# ROME.net
KiCad netlist of a schematic drawn in EAGLE
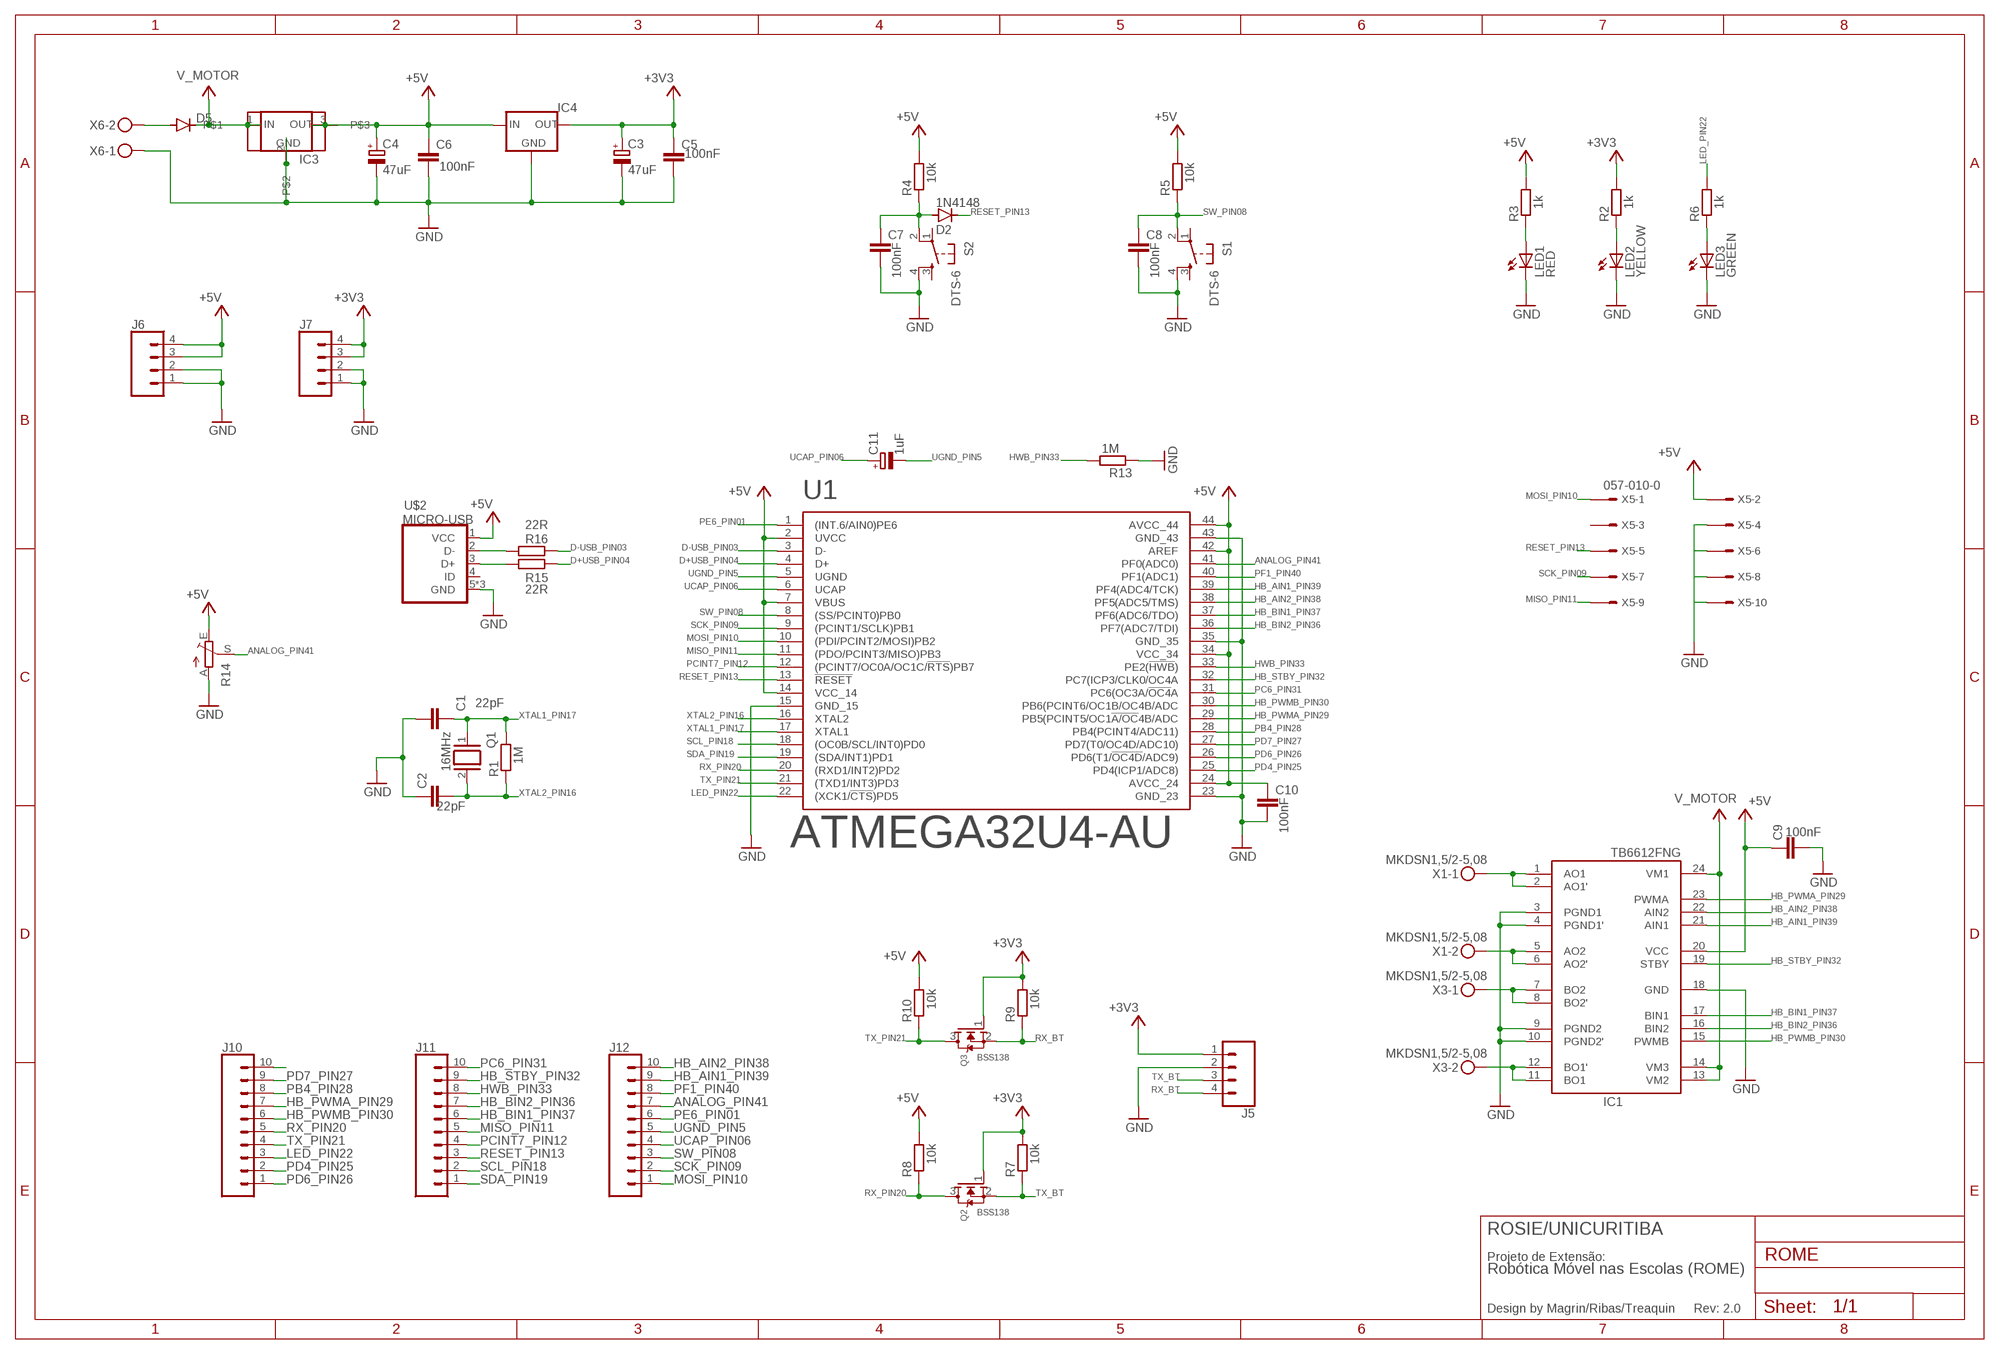
[diagram p0: schematic, sheet 1]

(export (version "E")
  (design (tool "Eeschema 10.0.6"))
  (components
    (comp (ref "C1")
      (value "22pF")
      (footprint "eagle-import:C0805")
      (libsource (lib "eagle-import") (part "C-EUC0805"))
    )
    (comp (ref "C2")
      (value "22pF")
      (footprint "eagle-import:C0805")
      (libsource (lib "eagle-import") (part "C-EUC0805"))
    )
    (comp (ref "C3")
      (value "47uF")
      (footprint "eagle-import:PANASONIC_C")
      (libsource (lib "eagle-import") (part "CPOL-EUC"))
    )
    (comp (ref "C4")
      (value "47uF")
      (footprint "eagle-import:PANASONIC_C")
      (libsource (lib "eagle-import") (part "CPOL-EUC"))
    )
    (comp (ref "C5")
      (value "100nF")
      (footprint "eagle-import:C0805")
      (libsource (lib "eagle-import") (part "C-EUC0805"))
    )
    (comp (ref "C6")
      (value "100nF")
      (footprint "eagle-import:C0805")
      (libsource (lib "eagle-import") (part "C-EUC0805"))
    )
    (comp (ref "C7")
      (value "100nF")
      (footprint "eagle-import:C0805")
      (libsource (lib "eagle-import") (part "C-EUC0805"))
    )
    (comp (ref "C8")
      (value "100nF")
      (footprint "eagle-import:C0805")
      (libsource (lib "eagle-import") (part "C-EUC0805"))
    )
    (comp (ref "C9")
      (value "100nF")
      (footprint "eagle-import:C0805")
      (libsource (lib "eagle-import") (part "C-EUC0805"))
    )
    (comp (ref "C10")
      (value "100nF")
      (footprint "eagle-import:C0805")
      (libsource (lib "eagle-import") (part "C-EUC0805"))
    )
    (comp (ref "C11")
      (value "1uF")
      (footprint "eagle-import:PANASONIC_C")
      (libsource (lib "eagle-import") (part "CPOL-EUC"))
    )
    (comp (ref "D2")
      (value "1N4148")
      (footprint "eagle-import:SOD80C")
      (libsource (lib "eagle-import") (part "DIODE-SOD80C"))
    )
    (comp (ref "D5")
      (value "DIODE-DO214AC")
      (footprint "eagle-import:DO214AC")
      (libsource (lib "eagle-import") (part "DIODE-DO214AC"))
    )
    (comp (ref "IC1")
      (value "TB6612FNG")
      (footprint "eagle-import:SSOP24")
      (libsource (lib "eagle-import") (part "TB6612FNG"))
    )
    (comp (ref "IC3")
      (value "78XXS")
      (footprint "eagle-import:78XXS")
      (libsource (lib "eagle-import") (part "78XXS"))
    )
    (comp (ref "IC4")
      (value "LM1117MP-3.3")
      (footprint "eagle-import:SOT223")
      (fields (field (name "MF") "Texas Instruments"))
      (libsource (lib "eagle-import") (part "LM1117?-MP3.3"))
    )
    (comp (ref "J5")
      (value "CONN_04PTH")
      (footprint "eagle-import:1X04")
      (libsource (lib "eagle-import") (part "CONN_04PTH"))
    )
    (comp (ref "J6")
      (value "CONN_04PTH")
      (footprint "eagle-import:1X04")
      (libsource (lib "eagle-import") (part "CONN_04PTH"))
    )
    (comp (ref "J7")
      (value "CONN_04PTH")
      (footprint "eagle-import:1X04")
      (libsource (lib "eagle-import") (part "CONN_04PTH"))
    )
    (comp (ref "J10")
      (value "CONN_10\"")
      (footprint "eagle-import:1X10")
      (libsource (lib "eagle-import") (part "CONN_10{dblquote}"))
    )
    (comp (ref "J11")
      (value "CONN_10\"")
      (footprint "eagle-import:1X10")
      (libsource (lib "eagle-import") (part "CONN_10{dblquote}"))
    )
    (comp (ref "J12")
      (value "CONN_10\"")
      (footprint "eagle-import:1X10")
      (libsource (lib "eagle-import") (part "CONN_10{dblquote}"))
    )
    (comp (ref "LED1")
      (value "RED")
      (footprint "eagle-import:CHIPLED_0805")
      (libsource (lib "eagle-import") (part "LEDCHIPLED_0805"))
    )
    (comp (ref "LED2")
      (value "YELLOW")
      (footprint "eagle-import:CHIPLED_0805")
      (libsource (lib "eagle-import") (part "LEDCHIPLED_0805"))
    )
    (comp (ref "LED3")
      (value "GREEN")
      (footprint "eagle-import:CHIPLED_0805")
      (libsource (lib "eagle-import") (part "LEDCHIPLED_0805"))
    )
    (comp (ref "Q1")
      (value "16MHz")
      (footprint "eagle-import:QS")
      (libsource (lib "eagle-import") (part "XTAL/S"))
    )
    (comp (ref "Q2")
      (value "BSS138")
      (footprint "eagle-import:SOT23")
      (libsource (lib "eagle-import") (part "MOSFET-NREFLOW"))
    )
    (comp (ref "Q3")
      (value "BSS138")
      (footprint "eagle-import:SOT23")
      (libsource (lib "eagle-import") (part "MOSFET-NREFLOW"))
    )
    (comp (ref "R1")
      (value "1M")
      (footprint "eagle-import:R0805")
      (libsource (lib "eagle-import") (part "R-EU_R0805"))
    )
    (comp (ref "R2")
      (value "1k")
      (footprint "eagle-import:R0805")
      (libsource (lib "eagle-import") (part "R-EU_R0805"))
    )
    (comp (ref "R3")
      (value "1k")
      (footprint "eagle-import:R0805")
      (libsource (lib "eagle-import") (part "R-EU_R0805"))
    )
    (comp (ref "R4")
      (value "10k")
      (footprint "eagle-import:R0805")
      (libsource (lib "eagle-import") (part "R-EU_R0805"))
    )
    (comp (ref "R5")
      (value "10k")
      (footprint "eagle-import:R0805")
      (libsource (lib "eagle-import") (part "R-EU_R0805"))
    )
    (comp (ref "R6")
      (value "1k")
      (footprint "eagle-import:R0805")
      (libsource (lib "eagle-import") (part "R-EU_R0805"))
    )
    (comp (ref "R7")
      (value "10k")
      (footprint "eagle-import:R0805")
      (libsource (lib "eagle-import") (part "R-EU_R0805"))
    )
    (comp (ref "R8")
      (value "10k")
      (footprint "eagle-import:R0805")
      (libsource (lib "eagle-import") (part "R-EU_R0805"))
    )
    (comp (ref "R9")
      (value "10k")
      (footprint "eagle-import:R0805")
      (libsource (lib "eagle-import") (part "R-EU_R0805"))
    )
    (comp (ref "R10")
      (value "10k")
      (footprint "eagle-import:R0805")
      (libsource (lib "eagle-import") (part "R-EU_R0805"))
    )
    (comp (ref "R13")
      (value "1M")
      (footprint "eagle-import:R0805")
      (libsource (lib "eagle-import") (part "R-EU_R0805"))
    )
    (comp (ref "R14")
      (value "TRIM_EU-CA6V")
      (footprint "eagle-import:CA6V")
      (libsource (lib "eagle-import") (part "TRIM_EU-CA6V"))
    )
    (comp (ref "R15")
      (value "22R")
      (footprint "eagle-import:R0805")
      (libsource (lib "eagle-import") (part "R-EU_R0805"))
    )
    (comp (ref "R16")
      (value "22R")
      (footprint "eagle-import:R0805")
      (libsource (lib "eagle-import") (part "R-EU_R0805"))
    )
    (comp (ref "S1")
      (value "DTS-6")
      (footprint "eagle-import:DTS-6")
      (libsource (lib "eagle-import") (part "DTS-6"))
    )
    (comp (ref "S2")
      (value "DTS-6")
      (footprint "eagle-import:DTS-6")
      (libsource (lib "eagle-import") (part "DTS-6"))
    )
    (comp (ref "U$2")
      (value "MICRO-USB")
      (footprint "eagle-import:MICRO-USB")
      (libsource (lib "eagle-import") (part "MICRO-USB"))
    )
    (comp (ref "U$4")
      (value "DPACK")
      (footprint "eagle-import:DPACK")
      (libsource (lib "eagle-import") (part "DPACK"))
    )
    (comp (ref "U1")
      (value "ATMEGA32U4-AU")
      (footprint "eagle-import:44-TQFP")
      (fields
        (field (name "DIGIKEY_PART_NUMBER") "ATMEGA32U4-AU-ND")
        (field (name "MANUFACTURER") "Microchip Technology")
        (field (name "CREATED_BY") "PCBLayout.com")
      )
      (libsource (lib "eagle-import") (part "ATMEGA32U4-AU"))
    )
    (comp (ref "X1")
      (value "MKDSN1,5/2-5,08")
      (footprint "eagle-import:MKDSN1,5_2-5,08")
      (libsource (lib "eagle-import") (part "MKDSN1,5/2-5,08"))
    )
    (comp (ref "X3")
      (value "MKDSN1,5/2-5,08")
      (footprint "eagle-import:MKDSN1,5_2-5,08")
      (libsource (lib "eagle-import") (part "MKDSN1,5/2-5,08"))
    )
    (comp (ref "X5")
      (value "057-010-0")
      (footprint "eagle-import:057-010-0")
      (libsource (lib "eagle-import") (part "057-010-0"))
    )
    (comp (ref "X6")
      (value "MKDSN1,5/2-5,08")
      (footprint "eagle-import:MKDSN1,5_2-5,08")
      (libsource (lib "eagle-import") (part "MKDSN1,5/2-5,08"))
    )
  )
  (nets
    (net (code "1") (name "+3V3") (class "Default")
      (node (ref "C3") (pin "+") (pinfunction "+_+") (pintype "passive"))
      (node (ref "C5") (pin "1") (pinfunction "1_1") (pintype "passive"))
      (node (ref "IC4") (pin "2") (pinfunction "OUT_2") (pintype "passive"))
      (node (ref "IC4") (pin "4") (pinfunction "OUT_4") (pintype "passive"))
      (node (ref "J5") (pin "1") (pinfunction "1_1") (pintype "passive"))
      (node (ref "J7") (pin "3") (pinfunction "3_3") (pintype "passive"))
      (node (ref "J7") (pin "4") (pinfunction "4_4") (pintype "passive"))
      (node (ref "Q2") (pin "1") (pinfunction "G_1") (pintype "bidirectional"))
      (node (ref "Q3") (pin "1") (pinfunction "G_1") (pintype "bidirectional"))
      (node (ref "R2") (pin "2") (pinfunction "2_2") (pintype "passive"))
      (node (ref "R7") (pin "2") (pinfunction "2_2") (pintype "passive"))
      (node (ref "R9") (pin "2") (pinfunction "2_2") (pintype "passive"))
    )
    (net (code "2") (name "+5V") (class "Default")
      (node (ref "C10") (pin "1") (pinfunction "1_1") (pintype "passive"))
      (node (ref "C4") (pin "+") (pinfunction "+_+") (pintype "passive"))
      (node (ref "C6") (pin "1") (pinfunction "1_1") (pintype "passive"))
      (node (ref "C9") (pin "1") (pinfunction "1_1") (pintype "passive"))
      (node (ref "IC1") (pin "20") (pinfunction "VCC_20") (pintype "power_in"))
      (node (ref "IC3") (pin "OUT") (pinfunction "OUT_OUT") (pintype "passive"))
      (node (ref "IC4") (pin "3") (pinfunction "IN_3") (pintype "input"))
      (node (ref "J6") (pin "3") (pinfunction "3_3") (pintype "passive"))
      (node (ref "J6") (pin "4") (pinfunction "4_4") (pintype "passive"))
      (node (ref "R10") (pin "2") (pinfunction "2_2") (pintype "passive"))
      (node (ref "R14") (pin "E") (pinfunction "E_E") (pintype "passive"))
      (node (ref "R3") (pin "2") (pinfunction "2_2") (pintype "passive"))
      (node (ref "R4") (pin "2") (pinfunction "2_2") (pintype "passive"))
      (node (ref "R5") (pin "2") (pinfunction "2_2") (pintype "passive"))
      (node (ref "R8") (pin "2") (pinfunction "2_2") (pintype "passive"))
      (node (ref "U$2") (pin "1") (pinfunction "VCC_1") (pintype "power_in"))
      (node (ref "U$4") (pin "3") (pinfunction "P$3_3") (pintype "bidirectional"))
      (node (ref "U1") (pin "14") (pinfunction "VCC_14_14") (pintype "power_in"))
      (node (ref "U1") (pin "2") (pinfunction "UVCC_2") (pintype "power_in"))
      (node (ref "U1") (pin "24") (pinfunction "AVCC_24_24") (pintype "power_in"))
      (node (ref "U1") (pin "34") (pinfunction "VCC_34_34") (pintype "power_in"))
      (node (ref "U1") (pin "42") (pinfunction "AREF_42") (pintype "input"))
      (node (ref "U1") (pin "44") (pinfunction "AVCC_44_44") (pintype "power_in"))
      (node (ref "U1") (pin "7") (pinfunction "VBUS_7") (pintype "input"))
      (node (ref "X5") (pin "2") (pinfunction "S_2") (pintype "passive"))
    )
    (net (code "3") (name "/ANALOG_PIN41") (class "Default")
      (node (ref "J12") (pin "7") (pinfunction "7_7") (pintype "passive"))
      (node (ref "R14") (pin "S") (pinfunction "S_S") (pintype "passive"))
      (node (ref "U1") (pin "41") (pinfunction "PF0(ADC0)_41") (pintype "bidirectional"))
    )
    (net (code "4") (name "/D+USB_PIN04") (class "Default")
      (node (ref "R15") (pin "2") (pinfunction "2_2") (pintype "passive"))
      (node (ref "U1") (pin "4") (pinfunction "D+_4") (pintype "input"))
    )
    (net (code "5") (name "/D-USB_PIN03") (class "Default")
      (node (ref "R16") (pin "2") (pinfunction "2_2") (pintype "passive"))
      (node (ref "U1") (pin "3") (pinfunction "D-_3") (pintype "input"))
    )
    (net (code "6") (name "/HB_AIN1_PIN39") (class "Default")
      (node (ref "IC1") (pin "21") (pinfunction "AIN1_21") (pintype "input"))
      (node (ref "J12") (pin "9") (pinfunction "9_9") (pintype "passive"))
      (node (ref "U1") (pin "39") (pinfunction "PF4(ADC4/TCK)_39") (pintype "bidirectional"))
    )
    (net (code "7") (name "/HB_AIN2_PIN38") (class "Default")
      (node (ref "IC1") (pin "22") (pinfunction "AIN2_22") (pintype "input"))
      (node (ref "J12") (pin "10") (pinfunction "10_10") (pintype "passive"))
      (node (ref "U1") (pin "38") (pinfunction "PF5(ADC5/TMS)_38") (pintype "bidirectional"))
    )
    (net (code "8") (name "/HB_BIN1_PIN37") (class "Default")
      (node (ref "IC1") (pin "17") (pinfunction "BIN1_17") (pintype "input"))
      (node (ref "J11") (pin "6") (pinfunction "6_6") (pintype "passive"))
      (node (ref "U1") (pin "37") (pinfunction "PF6(ADC6/TDO)_37") (pintype "bidirectional"))
    )
    (net (code "9") (name "/HB_BIN2_PIN36") (class "Default")
      (node (ref "IC1") (pin "16") (pinfunction "BIN2_16") (pintype "input"))
      (node (ref "J11") (pin "7") (pinfunction "7_7") (pintype "passive"))
      (node (ref "U1") (pin "36") (pinfunction "PF7(ADC7/TDI)_36") (pintype "bidirectional"))
    )
    (net (code "10") (name "/HB_PWMA_PIN29") (class "Default")
      (node (ref "IC1") (pin "23") (pinfunction "PWMA_23") (pintype "input"))
      (node (ref "J10") (pin "7") (pinfunction "7_7") (pintype "passive"))
      (node (ref "U1") (pin "29") (pinfunction "PB5(PCINT5/OC1~{A/OC}4B/ADC_29") (pintype "bidirectional"))
    )
    (net (code "11") (name "/HB_PWMB_PIN30") (class "Default")
      (node (ref "IC1") (pin "15") (pinfunction "PWMB_15") (pintype "input"))
      (node (ref "J10") (pin "6") (pinfunction "6_6") (pintype "passive"))
      (node (ref "U1") (pin "30") (pinfunction "PB6(PCINT6/OC1B/OC4B/ADC_30") (pintype "bidirectional"))
    )
    (net (code "12") (name "/HB_STBY_PIN32") (class "Default")
      (node (ref "IC1") (pin "19") (pinfunction "STBY_19") (pintype "input"))
      (node (ref "J11") (pin "9") (pinfunction "9_9") (pintype "passive"))
      (node (ref "U1") (pin "32") (pinfunction "PC7(ICP3/CLK0/OC4A_32") (pintype "bidirectional"))
    )
    (net (code "13") (name "/HWB_PIN33") (class "Default")
      (node (ref "J11") (pin "8") (pinfunction "8_8") (pintype "passive"))
      (node (ref "R13") (pin "2") (pinfunction "2_2") (pintype "passive"))
      (node (ref "U1") (pin "33") (pinfunction "PE2(~{HWB})_33") (pintype "bidirectional"))
    )
    (net (code "14") (name "/LED_PIN22") (class "Default")
      (node (ref "J10") (pin "3") (pinfunction "3_3") (pintype "passive"))
      (node (ref "R6") (pin "2") (pinfunction "2_2") (pintype "passive"))
      (node (ref "U1") (pin "22") (pinfunction "(XCK1/~{CTS})PD5_22") (pintype "bidirectional"))
    )
    (net (code "15") (name "/MISO_PIN11") (class "Default")
      (node (ref "J11") (pin "5") (pinfunction "5_5") (pintype "passive"))
      (node (ref "U1") (pin "11") (pinfunction "(PDO/PCINT3/MISO)PB3_11") (pintype "bidirectional"))
      (node (ref "X5") (pin "9") (pinfunction "S_9") (pintype "passive"))
    )
    (net (code "16") (name "/MOSI_PIN10") (class "Default")
      (node (ref "J12") (pin "1") (pinfunction "1_1") (pintype "passive"))
      (node (ref "U1") (pin "10") (pinfunction "(PDI/PCINT2/MOSI)PB2_10") (pintype "bidirectional"))
      (node (ref "X5") (pin "1") (pinfunction "S_1") (pintype "passive"))
    )
    (net (code "17") (name "/PB4_PIN28") (class "Default")
      (node (ref "J10") (pin "8") (pinfunction "8_8") (pintype "passive"))
      (node (ref "U1") (pin "28") (pinfunction "PB4(PCINT4/ADC11)_28") (pintype "bidirectional"))
    )
    (net (code "18") (name "/PC6_PIN31") (class "Default")
      (node (ref "J11") (pin "10") (pinfunction "10_10") (pintype "passive"))
      (node (ref "U1") (pin "31") (pinfunction "PC6(OC3A/~{OC4}A_31") (pintype "bidirectional"))
    )
    (net (code "19") (name "/PCINT7_PIN12") (class "Default")
      (node (ref "J11") (pin "4") (pinfunction "4_4") (pintype "passive"))
      (node (ref "U1") (pin "12") (pinfunction "(PCINT7/OC0A/OC1C/~{RTS})PB7_12") (pintype "bidirectional"))
    )
    (net (code "20") (name "/PD4_PIN25") (class "Default")
      (node (ref "J10") (pin "2") (pinfunction "2_2") (pintype "passive"))
      (node (ref "U1") (pin "25") (pinfunction "PD4(ICP1/ADC8)_25") (pintype "bidirectional"))
    )
    (net (code "21") (name "/PD6_PIN26") (class "Default")
      (node (ref "J10") (pin "1") (pinfunction "1_1") (pintype "passive"))
      (node (ref "U1") (pin "26") (pinfunction "PD6(T1/~{OC4D}/ADC9)_26") (pintype "bidirectional"))
    )
    (net (code "22") (name "/PD7_PIN27") (class "Default")
      (node (ref "J10") (pin "9") (pinfunction "9_9") (pintype "passive"))
      (node (ref "U1") (pin "27") (pinfunction "PD7(T0/OC4D/ADC10)_27") (pintype "bidirectional"))
    )
    (net (code "23") (name "/PE6_PIN01") (class "Default")
      (node (ref "J12") (pin "6") (pinfunction "6_6") (pintype "passive"))
      (node (ref "U1") (pin "1") (pinfunction "(INT.6/AIN0)PE6_1") (pintype "bidirectional"))
    )
    (net (code "24") (name "/PF1_PIN40") (class "Default")
      (node (ref "J12") (pin "8") (pinfunction "8_8") (pintype "passive"))
      (node (ref "U1") (pin "40") (pinfunction "PF1(ADC1)_40") (pintype "bidirectional"))
    )
    (net (code "25") (name "/RESET_PIN13") (class "Default")
      (node (ref "D2") (pin "C") (pinfunction "C_C") (pintype "passive"))
      (node (ref "J11") (pin "3") (pinfunction "3_3") (pintype "passive"))
      (node (ref "U1") (pin "13") (pinfunction "~{RESET}_13") (pintype "input"))
      (node (ref "X5") (pin "5") (pinfunction "S_5") (pintype "passive"))
    )
    (net (code "26") (name "/RX_BT") (class "Default")
      (node (ref "J5") (pin "4") (pinfunction "4_4") (pintype "passive"))
      (node (ref "Q3") (pin "2") (pinfunction "S_2") (pintype "bidirectional"))
      (node (ref "R9") (pin "1") (pinfunction "1_1") (pintype "passive"))
    )
    (net (code "27") (name "/RX_PIN20") (class "Default")
      (node (ref "J10") (pin "5") (pinfunction "5_5") (pintype "passive"))
      (node (ref "Q2") (pin "3") (pinfunction "D_3") (pintype "bidirectional"))
      (node (ref "R8") (pin "1") (pinfunction "1_1") (pintype "passive"))
      (node (ref "U1") (pin "20") (pinfunction "(RXD1/INT2)PD2_20") (pintype "bidirectional"))
    )
    (net (code "28") (name "/SCK_PIN09") (class "Default")
      (node (ref "J12") (pin "2") (pinfunction "2_2") (pintype "passive"))
      (node (ref "U1") (pin "9") (pinfunction "(PCINT1/SCLK)PB1_9") (pintype "bidirectional"))
      (node (ref "X5") (pin "7") (pinfunction "S_7") (pintype "passive"))
    )
    (net (code "29") (name "/SCL_PIN18") (class "Default")
      (node (ref "J11") (pin "2") (pinfunction "2_2") (pintype "passive"))
      (node (ref "U1") (pin "18") (pinfunction "(OC0B/SCL/INT0)PD0_18") (pintype "bidirectional"))
    )
    (net (code "30") (name "/SDA_PIN19") (class "Default")
      (node (ref "J11") (pin "1") (pinfunction "1_1") (pintype "passive"))
      (node (ref "U1") (pin "19") (pinfunction "(SDA/INT1)PD1_19") (pintype "bidirectional"))
    )
    (net (code "31") (name "/SW_PIN08") (class "Default")
      (node (ref "C8") (pin "1") (pinfunction "1_1") (pintype "passive"))
      (node (ref "J12") (pin "3") (pinfunction "3_3") (pintype "passive"))
      (node (ref "R5") (pin "1") (pinfunction "1_1") (pintype "passive"))
      (node (ref "S1") (pin "2") (pinfunction "2_2") (pintype "passive"))
      (node (ref "U1") (pin "8") (pinfunction "(SS/PCINT0)PB0_8") (pintype "bidirectional"))
    )
    (net (code "32") (name "/TX_BT") (class "Default")
      (node (ref "J5") (pin "3") (pinfunction "3_3") (pintype "passive"))
      (node (ref "Q2") (pin "2") (pinfunction "S_2") (pintype "bidirectional"))
      (node (ref "R7") (pin "1") (pinfunction "1_1") (pintype "passive"))
    )
    (net (code "33") (name "/TX_PIN21") (class "Default")
      (node (ref "J10") (pin "4") (pinfunction "4_4") (pintype "passive"))
      (node (ref "Q3") (pin "3") (pinfunction "D_3") (pintype "bidirectional"))
      (node (ref "R10") (pin "1") (pinfunction "1_1") (pintype "passive"))
      (node (ref "U1") (pin "21") (pinfunction "(TXD1/INT3)PD3_21") (pintype "bidirectional"))
    )
    (net (code "34") (name "/UCAP_PIN06") (class "Default")
      (node (ref "C11") (pin "+") (pinfunction "+_+") (pintype "passive"))
      (node (ref "J12") (pin "4") (pinfunction "4_4") (pintype "passive"))
      (node (ref "U1") (pin "6") (pinfunction "UCAP_6") (pintype "power_in"))
    )
    (net (code "35") (name "/UGND_PIN5") (class "Default")
      (node (ref "C11") (pin "-") (pinfunction "-_-") (pintype "passive"))
      (node (ref "J12") (pin "5") (pinfunction "5_5") (pintype "passive"))
      (node (ref "U1") (pin "5") (pinfunction "UGND_5") (pintype "power_in"))
    )
    (net (code "36") (name "/XTAL1_PIN17") (class "Default")
      (node (ref "C1") (pin "2") (pinfunction "2_2") (pintype "passive"))
      (node (ref "Q1") (pin "1") (pinfunction "1_1") (pintype "passive"))
      (node (ref "R1") (pin "2") (pinfunction "2_2") (pintype "passive"))
      (node (ref "U1") (pin "17") (pinfunction "XTAL1_17") (pintype "input"))
    )
    (net (code "37") (name "/XTAL2_PIN16") (class "Default")
      (node (ref "C2") (pin "2") (pinfunction "2_2") (pintype "passive"))
      (node (ref "Q1") (pin "2") (pinfunction "2_2") (pintype "passive"))
      (node (ref "R1") (pin "1") (pinfunction "1_1") (pintype "passive"))
      (node (ref "U1") (pin "16") (pinfunction "XTAL2_16") (pintype "output"))
    )
    (net (code "38") (name "GND") (class "Default")
      (node (ref "C1") (pin "1") (pinfunction "1_1") (pintype "passive"))
      (node (ref "C10") (pin "2") (pinfunction "2_2") (pintype "passive"))
      (node (ref "C2") (pin "1") (pinfunction "1_1") (pintype "passive"))
      (node (ref "C3") (pin "-") (pinfunction "-_-") (pintype "passive"))
      (node (ref "C4") (pin "-") (pinfunction "-_-") (pintype "passive"))
      (node (ref "C5") (pin "2") (pinfunction "2_2") (pintype "passive"))
      (node (ref "C6") (pin "2") (pinfunction "2_2") (pintype "passive"))
      (node (ref "C7") (pin "2") (pinfunction "2_2") (pintype "passive"))
      (node (ref "C8") (pin "2") (pinfunction "2_2") (pintype "passive"))
      (node (ref "C9") (pin "2") (pinfunction "2_2") (pintype "passive"))
      (node (ref "IC1") (pin "10") (pinfunction "PGND2'_10") (pintype "power_in"))
      (node (ref "IC1") (pin "18") (pinfunction "GND_18") (pintype "power_in"))
      (node (ref "IC1") (pin "3") (pinfunction "PGND1_3") (pintype "power_in"))
      (node (ref "IC1") (pin "4") (pinfunction "PGND1'_4") (pintype "power_in"))
      (node (ref "IC1") (pin "9") (pinfunction "PGND2_9") (pintype "power_in"))
      (node (ref "IC3") (pin "GND") (pinfunction "GND_GND") (pintype "input"))
      (node (ref "IC4") (pin "1") (pinfunction "GND_1") (pintype "input"))
      (node (ref "J5") (pin "2") (pinfunction "2_2") (pintype "passive"))
      (node (ref "J6") (pin "1") (pinfunction "1_1") (pintype "passive"))
      (node (ref "J6") (pin "2") (pinfunction "2_2") (pintype "passive"))
      (node (ref "J7") (pin "1") (pinfunction "1_1") (pintype "passive"))
      (node (ref "J7") (pin "2") (pinfunction "2_2") (pintype "passive"))
      (node (ref "LED1") (pin "C") (pinfunction "C_C") (pintype "passive"))
      (node (ref "LED2") (pin "C") (pinfunction "C_C") (pintype "passive"))
      (node (ref "LED3") (pin "C") (pinfunction "C_C") (pintype "passive"))
      (node (ref "R13") (pin "1") (pinfunction "1_1") (pintype "passive"))
      (node (ref "R14") (pin "A") (pinfunction "A_A") (pintype "passive"))
      (node (ref "S1") (pin "4") (pinfunction "4_4") (pintype "passive"))
      (node (ref "S2") (pin "4") (pinfunction "4_4") (pintype "passive"))
      (node (ref "U$2") (pin "5") (pinfunction "GND_5") (pintype "power_in"))
      (node (ref "U$2") (pin "GND1") (pinfunction "GND_GND1") (pintype "power_in"))
      (node (ref "U$2") (pin "GND2") (pinfunction "GND_GND2") (pintype "power_in"))
      (node (ref "U$4") (pin "2") (pinfunction "P$2_2") (pintype "bidirectional"))
      (node (ref "U1") (pin "15") (pinfunction "GND_15_15") (pintype "power_in"))
      (node (ref "U1") (pin "23") (pinfunction "GND_23_23") (pintype "power_in"))
      (node (ref "U1") (pin "35") (pinfunction "GND_35_35") (pintype "power_in"))
      (node (ref "U1") (pin "43") (pinfunction "GND_43_43") (pintype "power_in"))
      (node (ref "X5") (pin "10") (pinfunction "S_10") (pintype "passive"))
      (node (ref "X5") (pin "4") (pinfunction "S_4") (pintype "passive"))
      (node (ref "X5") (pin "6") (pinfunction "S_6") (pintype "passive"))
      (node (ref "X5") (pin "8") (pinfunction "S_8") (pintype "passive"))
      (node (ref "X6") (pin "1") (pinfunction "KL_1") (pintype "passive"))
    )
    (net (code "39") (name "Net-(C7-Pad1)") (class "Default")
      (node (ref "C7") (pin "1") (pinfunction "1_1") (pintype "passive"))
      (node (ref "D2") (pin "A") (pinfunction "A_A") (pintype "passive"))
      (node (ref "R4") (pin "1") (pinfunction "1_1") (pintype "passive"))
      (node (ref "S2") (pin "2") (pinfunction "2_2") (pintype "passive"))
    )
    (net (code "40") (name "Net-(IC1-AO1')") (class "Default")
      (node (ref "IC1") (pin "1") (pinfunction "AO1_1") (pintype "output"))
      (node (ref "IC1") (pin "2") (pinfunction "AO1'_2") (pintype "output"))
      (node (ref "X1") (pin "1") (pinfunction "KL_1") (pintype "passive"))
    )
    (net (code "41") (name "Net-(IC1-AO2')") (class "Default")
      (node (ref "IC1") (pin "5") (pinfunction "AO2_5") (pintype "output"))
      (node (ref "IC1") (pin "6") (pinfunction "AO2'_6") (pintype "output"))
      (node (ref "X1") (pin "2") (pinfunction "KL_2") (pintype "passive"))
    )
    (net (code "42") (name "Net-(IC1-BO1')") (class "Default")
      (node (ref "IC1") (pin "11") (pinfunction "BO1_11") (pintype "output"))
      (node (ref "IC1") (pin "12") (pinfunction "BO1'_12") (pintype "output"))
      (node (ref "X3") (pin "2") (pinfunction "KL_2") (pintype "passive"))
    )
    (net (code "43") (name "Net-(IC1-BO2')") (class "Default")
      (node (ref "IC1") (pin "7") (pinfunction "BO2_7") (pintype "output"))
      (node (ref "IC1") (pin "8") (pinfunction "BO2'_8") (pintype "output"))
      (node (ref "X3") (pin "1") (pinfunction "KL_1") (pintype "passive"))
    )
    (net (code "44") (name "Net-(LED1-PadA)") (class "Default")
      (node (ref "LED1") (pin "A") (pinfunction "A_A") (pintype "passive"))
      (node (ref "R3") (pin "1") (pinfunction "1_1") (pintype "passive"))
    )
    (net (code "45") (name "Net-(LED2-PadA)") (class "Default")
      (node (ref "LED2") (pin "A") (pinfunction "A_A") (pintype "passive"))
      (node (ref "R2") (pin "1") (pinfunction "1_1") (pintype "passive"))
    )
    (net (code "46") (name "Net-(LED3-PadA)") (class "Default")
      (node (ref "LED3") (pin "A") (pinfunction "A_A") (pintype "passive"))
      (node (ref "R6") (pin "1") (pinfunction "1_1") (pintype "passive"))
    )
    (net (code "47") (name "Net-(U$2-D+)") (class "Default")
      (node (ref "R15") (pin "1") (pinfunction "1_1") (pintype "passive"))
      (node (ref "U$2") (pin "3") (pinfunction "D+_3") (pintype "bidirectional"))
    )
    (net (code "48") (name "Net-(U$2-D-)") (class "Default")
      (node (ref "R16") (pin "1") (pinfunction "1_1") (pintype "passive"))
      (node (ref "U$2") (pin "2") (pinfunction "D-_2") (pintype "bidirectional"))
    )
    (net (code "49") (name "Net-(X6B-KL)") (class "Default")
      (node (ref "D5") (pin "A") (pinfunction "A_A") (pintype "passive"))
      (node (ref "X6") (pin "2") (pinfunction "KL_2") (pintype "passive"))
    )
    (net (code "50") (name "V_MOTOR") (class "Default")
      (node (ref "D5") (pin "C") (pinfunction "C_C") (pintype "passive"))
      (node (ref "IC1") (pin "13") (pinfunction "VM2_13") (pintype "power_in"))
      (node (ref "IC1") (pin "14") (pinfunction "VM3_14") (pintype "power_in"))
      (node (ref "IC1") (pin "24") (pinfunction "VM1_24") (pintype "power_in"))
      (node (ref "IC3") (pin "IN") (pinfunction "IN_IN") (pintype "input"))
      (node (ref "U$4") (pin "1") (pinfunction "P$1_1") (pintype "bidirectional"))
    )
    (net (code "51") (name "unconnected-(J10-Pad10)") (class "Default")
      (node (ref "J10") (pin "10") (pinfunction "10_10") (pintype "passive"))
    )
    (net (code "52") (name "unconnected-(S1-Pad1)") (class "Default")
      (node (ref "S1") (pin "1") (pinfunction "1_1") (pintype "passive"))
    )
    (net (code "53") (name "unconnected-(S1-Pad3)") (class "Default")
      (node (ref "S1") (pin "3") (pinfunction "3_3") (pintype "passive"))
    )
    (net (code "54") (name "unconnected-(S2-Pad1)") (class "Default")
      (node (ref "S2") (pin "1") (pinfunction "1_1") (pintype "passive"))
    )
    (net (code "55") (name "unconnected-(S2-Pad3)") (class "Default")
      (node (ref "S2") (pin "3") (pinfunction "3_3") (pintype "passive"))
    )
    (net (code "56") (name "unconnected-(U$2-ID-Pad4)") (class "Default")
      (node (ref "U$2") (pin "4") (pinfunction "ID_4") (pintype "bidirectional"))
    )
    (net (code "57") (name "unconnected-(X5D-S-Pad3)") (class "Default")
      (node (ref "X5") (pin "3") (pinfunction "S_3") (pintype "passive"))
    )
  )
)
